# cenx4-rev2-2.net
KiCad netlist of a schematic drawn in EAGLE
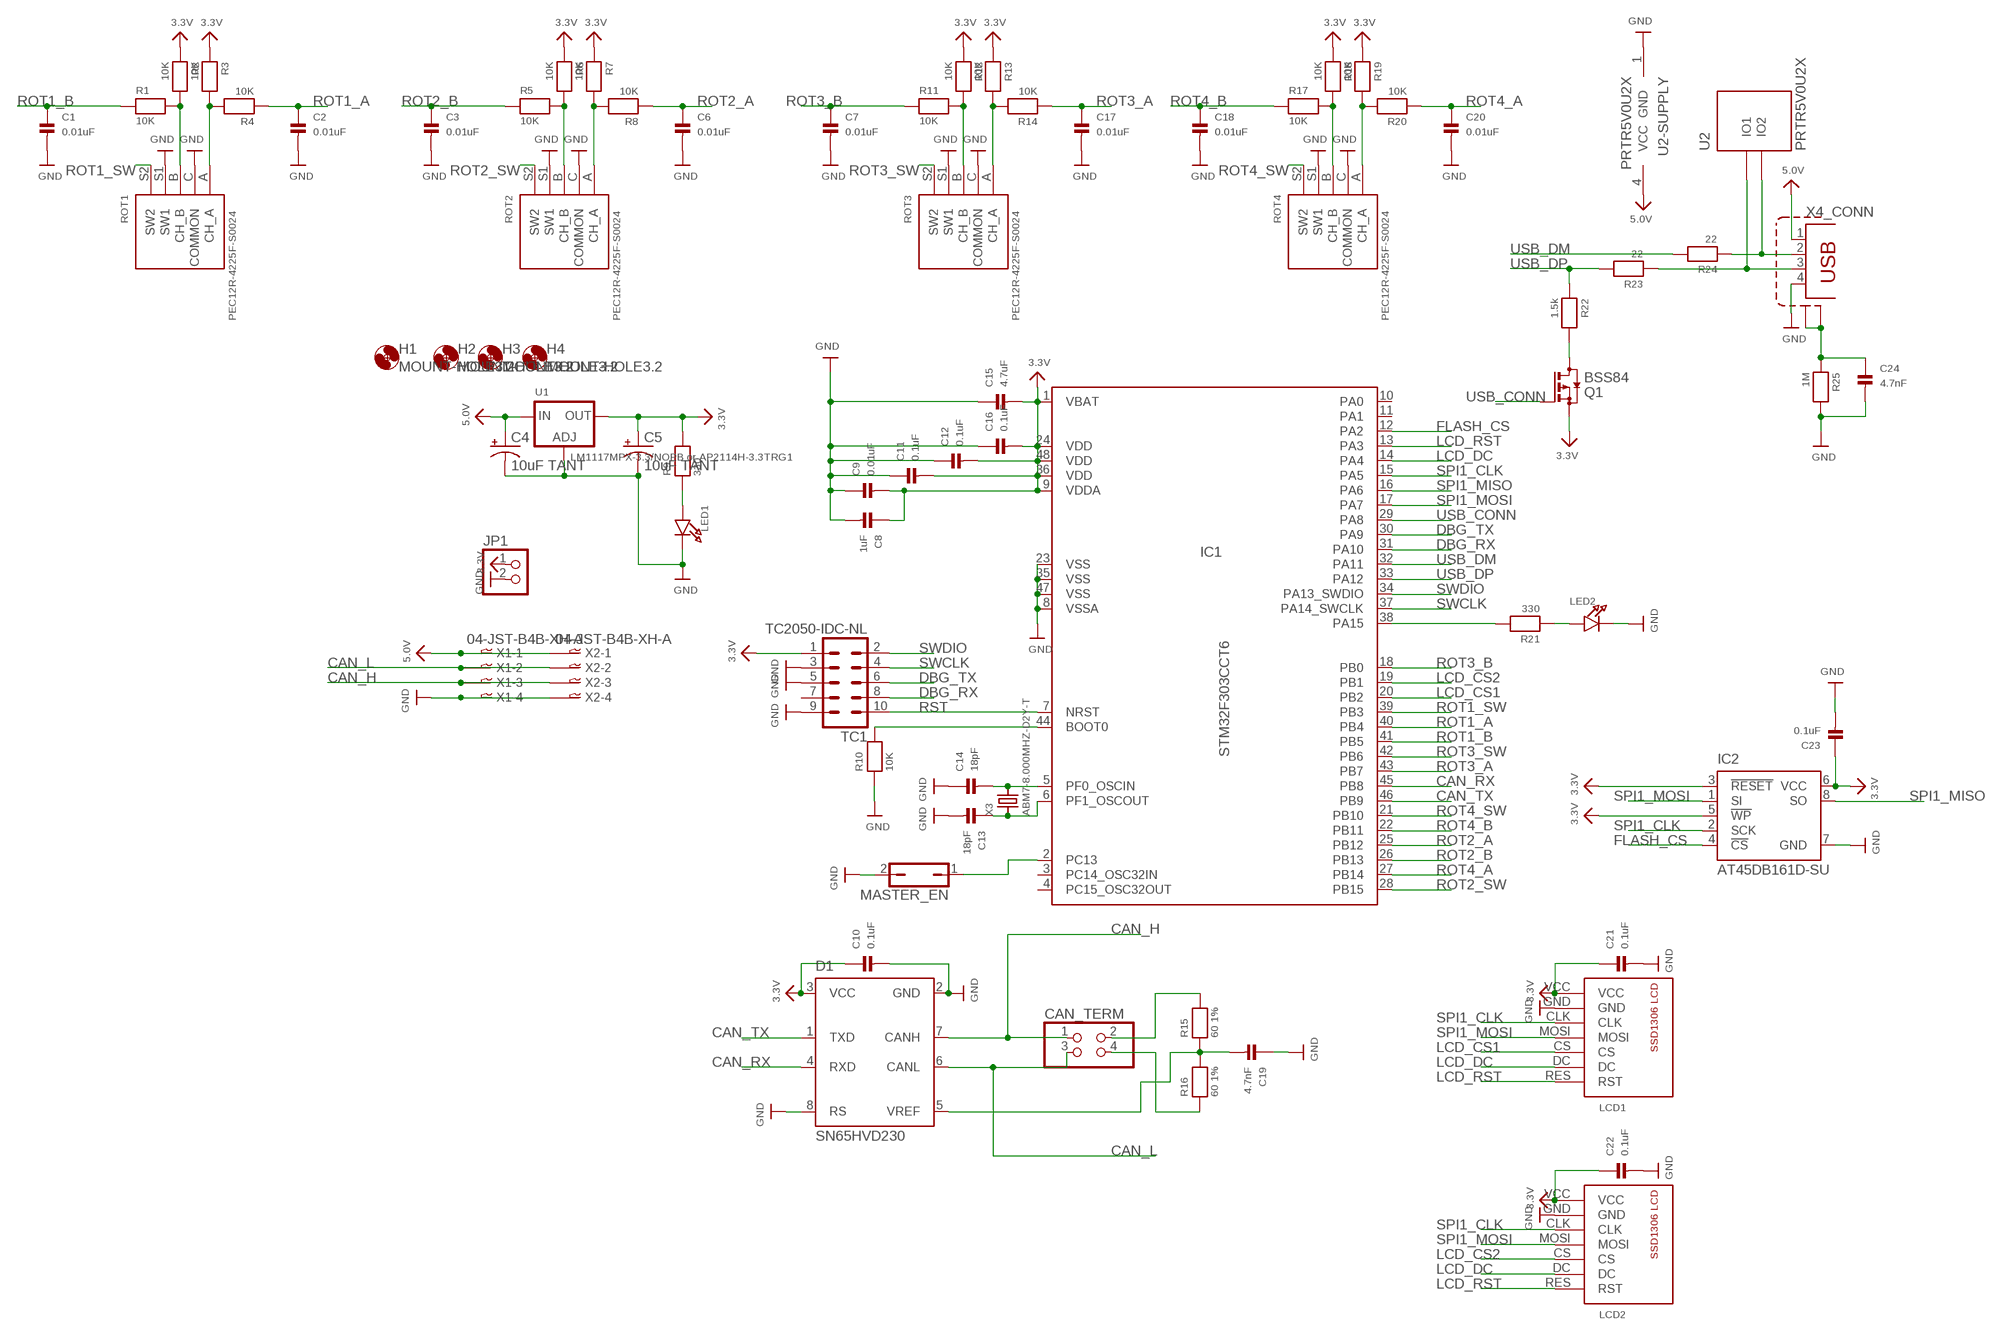
[diagram p0: schematic, sheet 1]

(export (version "E")
  (design (tool "Eeschema 10.0.6"))
  (components
    (comp (ref "C1")
      (value "0.01uF")
      (footprint "eagle-import:0603")
      (libsource (lib "eagle-import") (part "CAP_CERAMIC0603"))
    )
    (comp (ref "C2")
      (value "0.01uF")
      (footprint "eagle-import:0603")
      (libsource (lib "eagle-import") (part "CAP_CERAMIC0603"))
    )
    (comp (ref "C3")
      (value "0.01uF")
      (footprint "eagle-import:0603")
      (libsource (lib "eagle-import") (part "CAP_CERAMIC0603"))
    )
    (comp (ref "C4")
      (value "10uF TANT")
      (footprint "eagle-import:0603-POL")
      (libsource (lib "eagle-import") (part "10UF-6.3V-20%(0603)(TANT){dblquote}"))
    )
    (comp (ref "C5")
      (value "10uF TANT")
      (footprint "eagle-import:0603-POL")
      (libsource (lib "eagle-import") (part "10UF-6.3V-20%(0603)(TANT){dblquote}"))
    )
    (comp (ref "C6")
      (value "0.01uF")
      (footprint "eagle-import:0603")
      (libsource (lib "eagle-import") (part "CAP_CERAMIC0603"))
    )
    (comp (ref "C7")
      (value "0.01uF")
      (footprint "eagle-import:0603")
      (libsource (lib "eagle-import") (part "CAP_CERAMIC0603"))
    )
    (comp (ref "C8")
      (value "1uF")
      (footprint "eagle-import:0603")
      (libsource (lib "eagle-import") (part "CAP_CERAMIC0603"))
    )
    (comp (ref "C9")
      (value "0.01uF")
      (footprint "eagle-import:0603")
      (libsource (lib "eagle-import") (part "CAP_CERAMIC0603"))
    )
    (comp (ref "C10")
      (value "0.1uF")
      (footprint "eagle-import:0603")
      (libsource (lib "eagle-import") (part "CAP_CERAMIC0603"))
    )
    (comp (ref "C11")
      (value "0.1uF")
      (footprint "eagle-import:0603")
      (libsource (lib "eagle-import") (part "CAP_CERAMIC0603"))
    )
    (comp (ref "C12")
      (value "0.1uF")
      (footprint "eagle-import:0603")
      (libsource (lib "eagle-import") (part "CAP_CERAMIC0603"))
    )
    (comp (ref "C13")
      (value "18pF")
      (footprint "eagle-import:0603")
      (libsource (lib "eagle-import") (part "CAP_CERAMIC0603"))
    )
    (comp (ref "C14")
      (value "18pF")
      (footprint "eagle-import:0603")
      (libsource (lib "eagle-import") (part "CAP_CERAMIC0603"))
    )
    (comp (ref "C15")
      (value "4.7uF")
      (footprint "eagle-import:0603")
      (fields (field (name "MPN") "CL10A475MP5LNNC"))
      (libsource (lib "eagle-import") (part "CAP_CERAMIC0603"))
    )
    (comp (ref "C16")
      (value "0.1uF")
      (footprint "eagle-import:0603")
      (libsource (lib "eagle-import") (part "CAP_CERAMIC0603"))
    )
    (comp (ref "C17")
      (value "0.01uF")
      (footprint "eagle-import:0603")
      (libsource (lib "eagle-import") (part "CAP_CERAMIC0603"))
    )
    (comp (ref "C18")
      (value "0.01uF")
      (footprint "eagle-import:0603")
      (libsource (lib "eagle-import") (part "CAP_CERAMIC0603"))
    )
    (comp (ref "C19")
      (value "4.7nF")
      (footprint "eagle-import:0603")
      (libsource (lib "eagle-import") (part "CAP_CERAMIC0603"))
    )
    (comp (ref "C20")
      (value "0.01uF")
      (footprint "eagle-import:0603")
      (libsource (lib "eagle-import") (part "CAP_CERAMIC0603"))
    )
    (comp (ref "C21")
      (value "0.1uF")
      (footprint "eagle-import:0603")
      (libsource (lib "eagle-import") (part "CAP_CERAMIC0603"))
    )
    (comp (ref "C22")
      (value "0.1uF")
      (footprint "eagle-import:0603")
      (libsource (lib "eagle-import") (part "CAP_CERAMIC0603"))
    )
    (comp (ref "C23")
      (value "0.1uF")
      (footprint "eagle-import:0603")
      (libsource (lib "eagle-import") (part "CAP_CERAMIC0603"))
    )
    (comp (ref "C24")
      (value "4.7nF")
      (footprint "eagle-import:0603")
      (libsource (lib "eagle-import") (part "CAP_CERAMIC0603"))
    )
    (comp (ref "CAN_TERM")
      (value "PINHD-2X2")
      (footprint "eagle-import:2X02")
      (fields (field (name "MPN") "5-146254-2"))
      (libsource (lib "eagle-import") (part "PINHD-2X2"))
    )
    (comp (ref "D1")
      (value "SN65HVD230")
      (footprint "eagle-import:SO8")
      (fields (field (name "MPN") "SN65HVD230DR"))
      (libsource (lib "eagle-import") (part "SN65HVD230"))
    )
    (comp (ref "H1")
      (value "MOUNT-HOLE3.2")
      (footprint "eagle-import:3,2")
      (libsource (lib "eagle-import") (part "MOUNT-HOLE3.2"))
    )
    (comp (ref "H2")
      (value "MOUNT-HOLE3.2")
      (footprint "eagle-import:3,2")
      (libsource (lib "eagle-import") (part "MOUNT-HOLE3.2"))
    )
    (comp (ref "H3")
      (value "MOUNT-HOLE3.2")
      (footprint "eagle-import:3,2")
      (libsource (lib "eagle-import") (part "MOUNT-HOLE3.2"))
    )
    (comp (ref "H4")
      (value "MOUNT-HOLE3.2")
      (footprint "eagle-import:3,2")
      (libsource (lib "eagle-import") (part "MOUNT-HOLE3.2"))
    )
    (comp (ref "IC1")
      (value "STM32F303CCT6")
      (footprint "eagle-import:TQFP48")
      (libsource (lib "eagle-import") (part "STM32F302_F303_B_C_LQFP48"))
    )
    (comp (ref "IC2")
      (value "AT45DB161D-SU")
      (footprint "eagle-import:8S2")
      (fields (field (name "MF") "ATMEL"))
      (libsource (lib "eagle-import") (part "AT45DB161D-SU"))
    )
    (comp (ref "JP1")
      (value "PINHD-1X2")
      (footprint "eagle-import:1X02")
      (fields (field (name "MPN") "MF-CON-2.54mm-01x02"))
      (libsource (lib "eagle-import") (part "PINHD-1X2"))
    )
    (comp (ref "LCD1")
      (value "SSD1306-7PINWITHOUT-HOLES")
      (footprint "eagle-import:SSD1306-7PIN-NO-HOLES")
      (libsource (lib "eagle-import") (part "SSD1306-7PINWITHOUT-HOLES"))
    )
    (comp (ref "LCD2")
      (value "SSD1306-7PINWITHOUT-HOLES")
      (footprint "eagle-import:SSD1306-7PIN-NO-HOLES")
      (libsource (lib "eagle-import") (part "SSD1306-7PINWITHOUT-HOLES"))
    )
    (comp (ref "LED1")
      (value "LED0603")
      (footprint "eagle-import:CHIPLED_0603")
      (fields (field (name "MPN") "MF-LED-0603-GREEN"))
      (libsource (lib "eagle-import") (part "LED0603"))
    )
    (comp (ref "LED2")
      (value "LED0603")
      (footprint "eagle-import:CHIPLED_0603")
      (fields (field (name "MPN") "MF-LED-0603-GREEN"))
      (libsource (lib "eagle-import") (part "LED0603"))
    )
    (comp (ref "MASTER_EN")
      (value "JP1Q")
      (footprint "eagle-import:JP1")
      (fields (field (name "MPN") "MF-CON-2.54mm-01x02"))
      (libsource (lib "eagle-import") (part "JP1Q"))
    )
    (comp (ref "Q1")
      (value "BSS84")
      (footprint "eagle-import:SOT23")
      (libsource (lib "eagle-import") (part "BSS84"))
    )
    (comp (ref "R1")
      (value "10K")
      (footprint "eagle-import:0603")
      (libsource (lib "eagle-import") (part "RESISTOR0603"))
    )
    (comp (ref "R2")
      (value "10K")
      (footprint "eagle-import:0603")
      (libsource (lib "eagle-import") (part "RESISTOR0603"))
    )
    (comp (ref "R3")
      (value "10K")
      (footprint "eagle-import:0603")
      (libsource (lib "eagle-import") (part "RESISTOR0603"))
    )
    (comp (ref "R4")
      (value "10K")
      (footprint "eagle-import:0603")
      (libsource (lib "eagle-import") (part "RESISTOR0603"))
    )
    (comp (ref "R5")
      (value "10K")
      (footprint "eagle-import:0603")
      (libsource (lib "eagle-import") (part "RESISTOR0603"))
    )
    (comp (ref "R6")
      (value "10K")
      (footprint "eagle-import:0603")
      (libsource (lib "eagle-import") (part "RESISTOR0603"))
    )
    (comp (ref "R7")
      (value "10K")
      (footprint "eagle-import:0603")
      (libsource (lib "eagle-import") (part "RESISTOR0603"))
    )
    (comp (ref "R8")
      (value "10K")
      (footprint "eagle-import:0603")
      (libsource (lib "eagle-import") (part "RESISTOR0603"))
    )
    (comp (ref "R9")
      (value "330")
      (footprint "eagle-import:0603")
      (fields (field (name "MPN") "MF-RES-0603-330"))
      (libsource (lib "eagle-import") (part "RESISTOR0603"))
    )
    (comp (ref "R10")
      (value "10K")
      (footprint "eagle-import:0603")
      (libsource (lib "eagle-import") (part "RESISTOR0603"))
    )
    (comp (ref "R11")
      (value "10K")
      (footprint "eagle-import:0603")
      (libsource (lib "eagle-import") (part "RESISTOR0603"))
    )
    (comp (ref "R12")
      (value "10K")
      (footprint "eagle-import:0603")
      (libsource (lib "eagle-import") (part "RESISTOR0603"))
    )
    (comp (ref "R13")
      (value "10K")
      (footprint "eagle-import:0603")
      (libsource (lib "eagle-import") (part "RESISTOR0603"))
    )
    (comp (ref "R14")
      (value "10K")
      (footprint "eagle-import:0603")
      (libsource (lib "eagle-import") (part "RESISTOR0603"))
    )
    (comp (ref "R15")
      (value "60 1%")
      (footprint "eagle-import:0603")
      (fields (field (name "MPN") "MF-RES-0603-60.4"))
      (libsource (lib "eagle-import") (part "RESISTOR0603"))
    )
    (comp (ref "R16")
      (value "60 1%")
      (footprint "eagle-import:0603")
      (fields (field (name "MPN") "MF-RES-0603-60.4"))
      (libsource (lib "eagle-import") (part "RESISTOR0603"))
    )
    (comp (ref "R17")
      (value "10K")
      (footprint "eagle-import:0603")
      (libsource (lib "eagle-import") (part "RESISTOR0603"))
    )
    (comp (ref "R18")
      (value "10K")
      (footprint "eagle-import:0603")
      (libsource (lib "eagle-import") (part "RESISTOR0603"))
    )
    (comp (ref "R19")
      (value "10K")
      (footprint "eagle-import:0603")
      (libsource (lib "eagle-import") (part "RESISTOR0603"))
    )
    (comp (ref "R20")
      (value "10K")
      (footprint "eagle-import:0603")
      (libsource (lib "eagle-import") (part "RESISTOR0603"))
    )
    (comp (ref "R21")
      (value "330")
      (footprint "eagle-import:0603")
      (fields (field (name "MPN") "MF-RES-0603-330"))
      (libsource (lib "eagle-import") (part "RESISTOR0603"))
    )
    (comp (ref "R22")
      (value "1.5k")
      (footprint "eagle-import:0603")
      (fields (field (name "MPN") "MCR03ERTF1501"))
      (libsource (lib "eagle-import") (part "RESISTOR0603"))
    )
    (comp (ref "R23")
      (value "22")
      (footprint "eagle-import:0603")
      (fields (field (name "MPN") "MF-RES-0603-22"))
      (libsource (lib "eagle-import") (part "RESISTOR0603"))
    )
    (comp (ref "R24")
      (value "22")
      (footprint "eagle-import:0603")
      (fields (field (name "MPN") "MF-RES-0603-22"))
      (libsource (lib "eagle-import") (part "RESISTOR0603"))
    )
    (comp (ref "R25")
      (value "1M")
      (footprint "eagle-import:0603")
      (libsource (lib "eagle-import") (part "RESISTOR0603"))
    )
    (comp (ref "ROT1")
      (value "PEC12R-4225F-S0024")
      (footprint "eagle-import:PEC111-4XXXK-SXXXX")
      (libsource (lib "eagle-import") (part "PEC11-4215K-S0024"))
    )
    (comp (ref "ROT2")
      (value "PEC12R-4225F-S0024")
      (footprint "eagle-import:PEC111-4XXXK-SXXXX")
      (libsource (lib "eagle-import") (part "PEC11-4215K-S0024"))
    )
    (comp (ref "ROT3")
      (value "PEC12R-4225F-S0024")
      (footprint "eagle-import:PEC111-4XXXK-SXXXX")
      (libsource (lib "eagle-import") (part "PEC11-4215K-S0024"))
    )
    (comp (ref "ROT4")
      (value "PEC12R-4225F-S0024")
      (footprint "eagle-import:PEC111-4XXXK-SXXXX")
      (libsource (lib "eagle-import") (part "PEC11-4215K-S0024"))
    )
    (comp (ref "TC1")
      (value "TC2050-IDC-NL")
      (footprint "eagle-import:TC2050-IDC-NL")
      (libsource (lib "eagle-import") (part "TC2050-IDC-NL"))
    )
    (comp (ref "U1")
      (value "LM1117MPX-3.3/NOPB or AP2114H-3.3TRG1")
      (footprint "eagle-import:SOT223-R")
      (fields (field (name "MPN") "LM1117MPX-3.3/NOPB"))
      (libsource (lib "eagle-import") (part "LM1117SOT223-REFLOW"))
    )
    (comp (ref "U2")
      (value "PRTR5V0U2X")
      (footprint "eagle-import:SOT-143B")
      (fields (field (name "MANUFACTURER") "NXP Semiconductors") (field (name "MPN") "PRTR5V0U2X,215"))
      (libsource (lib "eagle-import") (part "PRTR5V0U2X?"))
    )
    (comp (ref "X1")
      (value "04-JST-B4B-XH-A")
      (footprint "eagle-import:B4B-XH")
      (fields (field (name "MPN") "B4B-XH-A(LF)(SN)"))
      (libsource (lib "eagle-import") (part "04-JST-B4B-XH-A"))
    )
    (comp (ref "X2")
      (value "04-JST-B4B-XH-A")
      (footprint "eagle-import:B4B-XH")
      (fields (field (name "MPN") "B4B-XH-A(LF)(SN)"))
      (libsource (lib "eagle-import") (part "04-JST-B4B-XH-A"))
    )
    (comp (ref "X3")
      (value "ABM7-8.000MHZ-D2Y-T")
      (footprint "eagle-import:ABM7-8.000MHZ-D2Y-T")
      (libsource (lib "eagle-import") (part "ABM7-8.000MHZ-D2Y-T"))
    )
    (comp (ref "X4")
      (value "TE-292304-1")
      (footprint "eagle-import:TE-292304-1")
      (fields (field (name "MPN") "292304-1 ") (field (name "POPULATE") "0"))
      (libsource (lib "eagle-import") (part "TE-292304-1"))
    )
  )
  (nets
    (net (code "1") (name "/CAN_H") (class "Default")
      (node (ref "CAN_TERM") (pin "1") (pinfunction "1_1") (pintype "passive"))
      (node (ref "D1") (pin "7") (pinfunction "CANH_7") (pintype "bidirectional"))
      (node (ref "X1") (pin "P$3") (pinfunction "1_P$3") (pintype "passive"))
      (node (ref "X2") (pin "P$3") (pinfunction "1_P$3") (pintype "passive"))
    )
    (net (code "2") (name "/CAN_L") (class "Default")
      (node (ref "CAN_TERM") (pin "3") (pinfunction "3_3") (pintype "passive"))
      (node (ref "D1") (pin "6") (pinfunction "CANL_6") (pintype "bidirectional"))
      (node (ref "X1") (pin "P$2") (pinfunction "1_P$2") (pintype "passive"))
      (node (ref "X2") (pin "P$2") (pinfunction "1_P$2") (pintype "passive"))
    )
    (net (code "3") (name "/CAN_RX") (class "Default")
      (node (ref "D1") (pin "4") (pinfunction "RXD_4") (pintype "output"))
      (node (ref "IC1") (pin "45") (pinfunction "PB8_45") (pintype "bidirectional"))
    )
    (net (code "4") (name "/CAN_TX") (class "Default")
      (node (ref "D1") (pin "1") (pinfunction "TXD_1") (pintype "input"))
      (node (ref "IC1") (pin "46") (pinfunction "PB9_46") (pintype "bidirectional"))
    )
    (net (code "5") (name "/DBG_RX") (class "Default")
      (node (ref "IC1") (pin "31") (pinfunction "PA10_31") (pintype "bidirectional"))
      (node (ref "TC1") (pin "8") (pinfunction "8_8") (pintype "passive"))
    )
    (net (code "6") (name "/DBG_TX") (class "Default")
      (node (ref "IC1") (pin "30") (pinfunction "PA9_30") (pintype "bidirectional"))
      (node (ref "TC1") (pin "6") (pinfunction "6_6") (pintype "passive"))
    )
    (net (code "7") (name "/FLASH_CS") (class "Default")
      (node (ref "IC1") (pin "12") (pinfunction "PA2_12") (pintype "bidirectional"))
      (node (ref "IC2") (pin "4") (pinfunction "~{CS}_4") (pintype "input"))
    )
    (net (code "8") (name "/LCD_CS1") (class "Default")
      (node (ref "IC1") (pin "20") (pinfunction "PB2_20") (pintype "bidirectional"))
      (node (ref "LCD1") (pin "CS") (pinfunction "CS_CS") (pintype "bidirectional"))
    )
    (net (code "9") (name "/LCD_CS2") (class "Default")
      (node (ref "IC1") (pin "19") (pinfunction "PB1_19") (pintype "bidirectional"))
      (node (ref "LCD2") (pin "CS") (pinfunction "CS_CS") (pintype "bidirectional"))
    )
    (net (code "10") (name "/LCD_DC") (class "Default")
      (node (ref "IC1") (pin "14") (pinfunction "PA4_14") (pintype "bidirectional"))
      (node (ref "LCD1") (pin "DC") (pinfunction "DC_DC") (pintype "bidirectional"))
      (node (ref "LCD2") (pin "DC") (pinfunction "DC_DC") (pintype "bidirectional"))
    )
    (net (code "11") (name "/LCD_RST") (class "Default")
      (node (ref "IC1") (pin "13") (pinfunction "PA3_13") (pintype "bidirectional"))
      (node (ref "LCD1") (pin "RES") (pinfunction "RST_RES") (pintype "bidirectional"))
      (node (ref "LCD2") (pin "RES") (pinfunction "RST_RES") (pintype "bidirectional"))
    )
    (net (code "12") (name "/ROT1_A") (class "Default")
      (node (ref "C2") (pin "1") (pinfunction "P$1_1") (pintype "passive"))
      (node (ref "IC1") (pin "40") (pinfunction "PB4_40") (pintype "input"))
      (node (ref "R4") (pin "1") (pinfunction "1_1") (pintype "passive"))
    )
    (net (code "13") (name "/ROT1_B") (class "Default")
      (node (ref "C1") (pin "1") (pinfunction "P$1_1") (pintype "passive"))
      (node (ref "IC1") (pin "41") (pinfunction "PB5_41") (pintype "bidirectional"))
      (node (ref "R1") (pin "1") (pinfunction "1_1") (pintype "passive"))
    )
    (net (code "14") (name "/ROT1_SW") (class "Default")
      (node (ref "IC1") (pin "39") (pinfunction "PB3_39") (pintype "output"))
      (node (ref "ROT1") (pin "S2") (pinfunction "SW2_S2") (pintype "bidirectional"))
    )
    (net (code "15") (name "/ROT2_A") (class "Default")
      (node (ref "C6") (pin "1") (pinfunction "P$1_1") (pintype "passive"))
      (node (ref "IC1") (pin "25") (pinfunction "PB12_25") (pintype "bidirectional"))
      (node (ref "R8") (pin "1") (pinfunction "1_1") (pintype "passive"))
    )
    (net (code "16") (name "/ROT2_B") (class "Default")
      (node (ref "C3") (pin "1") (pinfunction "P$1_1") (pintype "passive"))
      (node (ref "IC1") (pin "26") (pinfunction "PB13_26") (pintype "bidirectional"))
      (node (ref "R5") (pin "1") (pinfunction "1_1") (pintype "passive"))
    )
    (net (code "17") (name "/ROT2_SW") (class "Default")
      (node (ref "IC1") (pin "28") (pinfunction "PB15_28") (pintype "bidirectional"))
      (node (ref "ROT2") (pin "S2") (pinfunction "SW2_S2") (pintype "bidirectional"))
    )
    (net (code "18") (name "/ROT3_A") (class "Default")
      (node (ref "C17") (pin "1") (pinfunction "P$1_1") (pintype "passive"))
      (node (ref "IC1") (pin "43") (pinfunction "PB7_43") (pintype "bidirectional"))
      (node (ref "R14") (pin "1") (pinfunction "1_1") (pintype "passive"))
    )
    (net (code "19") (name "/ROT3_B") (class "Default")
      (node (ref "C7") (pin "1") (pinfunction "P$1_1") (pintype "passive"))
      (node (ref "IC1") (pin "18") (pinfunction "PB0_18") (pintype "bidirectional"))
      (node (ref "R11") (pin "1") (pinfunction "1_1") (pintype "passive"))
    )
    (net (code "20") (name "/ROT3_SW") (class "Default")
      (node (ref "IC1") (pin "42") (pinfunction "PB6_42") (pintype "bidirectional"))
      (node (ref "ROT3") (pin "S2") (pinfunction "SW2_S2") (pintype "bidirectional"))
    )
    (net (code "21") (name "/ROT4_A") (class "Default")
      (node (ref "C20") (pin "1") (pinfunction "P$1_1") (pintype "passive"))
      (node (ref "IC1") (pin "27") (pinfunction "PB14_27") (pintype "bidirectional"))
      (node (ref "R20") (pin "1") (pinfunction "1_1") (pintype "passive"))
    )
    (net (code "22") (name "/ROT4_B") (class "Default")
      (node (ref "C18") (pin "1") (pinfunction "P$1_1") (pintype "passive"))
      (node (ref "IC1") (pin "22") (pinfunction "PB11_22") (pintype "bidirectional"))
      (node (ref "R17") (pin "1") (pinfunction "1_1") (pintype "passive"))
    )
    (net (code "23") (name "/ROT4_SW") (class "Default")
      (node (ref "IC1") (pin "21") (pinfunction "PB10_21") (pintype "bidirectional"))
      (node (ref "ROT4") (pin "S2") (pinfunction "SW2_S2") (pintype "bidirectional"))
    )
    (net (code "24") (name "/RST") (class "Default")
      (node (ref "IC1") (pin "7") (pinfunction "NRST_7") (pintype "input"))
      (node (ref "TC1") (pin "10") (pinfunction "10_10") (pintype "passive"))
    )
    (net (code "25") (name "/SPI1_CLK") (class "Default")
      (node (ref "IC1") (pin "15") (pinfunction "PA5_15") (pintype "bidirectional"))
      (node (ref "IC2") (pin "2") (pinfunction "SCK_2") (pintype "input"))
      (node (ref "LCD1") (pin "CLK") (pinfunction "CLK_CLK") (pintype "bidirectional"))
      (node (ref "LCD2") (pin "CLK") (pinfunction "CLK_CLK") (pintype "bidirectional"))
    )
    (net (code "26") (name "/SPI1_MISO") (class "Default")
      (node (ref "IC1") (pin "16") (pinfunction "PA6_16") (pintype "bidirectional"))
      (node (ref "IC2") (pin "8") (pinfunction "SO_8") (pintype "output"))
    )
    (net (code "27") (name "/SPI1_MOSI") (class "Default")
      (node (ref "IC1") (pin "17") (pinfunction "PA7_17") (pintype "bidirectional"))
      (node (ref "IC2") (pin "1") (pinfunction "SI_1") (pintype "input"))
      (node (ref "LCD1") (pin "MOSI") (pinfunction "MOSI_MOSI") (pintype "bidirectional"))
      (node (ref "LCD2") (pin "MOSI") (pinfunction "MOSI_MOSI") (pintype "bidirectional"))
    )
    (net (code "28") (name "/SWCLK") (class "Default")
      (node (ref "IC1") (pin "37") (pinfunction "PA14_SWCLK_37") (pintype "input"))
      (node (ref "TC1") (pin "4") (pinfunction "4_4") (pintype "passive"))
    )
    (net (code "29") (name "/SWDIO") (class "Default")
      (node (ref "IC1") (pin "34") (pinfunction "PA13_SWDIO_34") (pintype "input"))
      (node (ref "TC1") (pin "2") (pinfunction "2_2") (pintype "passive"))
    )
    (net (code "30") (name "/USB_CONN") (class "Default")
      (node (ref "IC1") (pin "29") (pinfunction "PA8_29") (pintype "bidirectional"))
      (node (ref "Q1") (pin "1") (pinfunction "G_1") (pintype "passive"))
    )
    (net (code "31") (name "/USB_DM") (class "Default")
      (node (ref "IC1") (pin "32") (pinfunction "PA11_32") (pintype "bidirectional"))
      (node (ref "R24") (pin "2") (pinfunction "2_2") (pintype "passive"))
    )
    (net (code "32") (name "/USB_DP") (class "Default")
      (node (ref "IC1") (pin "33") (pinfunction "PA12_33") (pintype "bidirectional"))
      (node (ref "R22") (pin "1") (pinfunction "1_1") (pintype "passive"))
      (node (ref "R23") (pin "2") (pinfunction "2_2") (pintype "passive"))
    )
    (net (code "33") (name "3.3V") (class "Default")
      (node (ref "C10") (pin "1") (pinfunction "P$1_1") (pintype "passive"))
      (node (ref "C11") (pin "2") (pinfunction "P$2_2") (pintype "passive"))
      (node (ref "C12") (pin "2") (pinfunction "P$2_2") (pintype "passive"))
      (node (ref "C15") (pin "2") (pinfunction "P$2_2") (pintype "passive"))
      (node (ref "C16") (pin "2") (pinfunction "P$2_2") (pintype "passive"))
      (node (ref "C21") (pin "1") (pinfunction "P$1_1") (pintype "passive"))
      (node (ref "C22") (pin "1") (pinfunction "P$1_1") (pintype "passive"))
      (node (ref "C23") (pin "1") (pinfunction "P$1_1") (pintype "passive"))
      (node (ref "C5") (pin "A") (pinfunction "+_A") (pintype "passive"))
      (node (ref "C8") (pin "1") (pinfunction "P$1_1") (pintype "passive"))
      (node (ref "C9") (pin "2") (pinfunction "P$2_2") (pintype "passive"))
      (node (ref "D1") (pin "3") (pinfunction "VCC_3") (pintype "power_in"))
      (node (ref "IC1") (pin "1") (pinfunction "VBAT_1") (pintype "passive"))
      (node (ref "IC1") (pin "24") (pinfunction "VDD_24") (pintype "power_in"))
      (node (ref "IC1") (pin "36") (pinfunction "VDD_36") (pintype "power_in"))
      (node (ref "IC1") (pin "48") (pinfunction "VDD_48") (pintype "power_in"))
      (node (ref "IC1") (pin "9") (pinfunction "VDDA_9") (pintype "power_in"))
      (node (ref "IC2") (pin "3") (pinfunction "~{RESET}_3") (pintype "input"))
      (node (ref "IC2") (pin "5") (pinfunction "~{WP}_5") (pintype "input"))
      (node (ref "IC2") (pin "6") (pinfunction "VCC_6") (pintype "power_in"))
      (node (ref "JP1") (pin "1") (pinfunction "1_1") (pintype "passive"))
      (node (ref "LCD1") (pin "VCC") (pinfunction "VCC_VCC") (pintype "bidirectional"))
      (node (ref "LCD2") (pin "VCC") (pinfunction "VCC_VCC") (pintype "bidirectional"))
      (node (ref "Q1") (pin "2") (pinfunction "S_2") (pintype "passive"))
      (node (ref "R12") (pin "1") (pinfunction "1_1") (pintype "passive"))
      (node (ref "R13") (pin "1") (pinfunction "1_1") (pintype "passive"))
      (node (ref "R18") (pin "1") (pinfunction "1_1") (pintype "passive"))
      (node (ref "R19") (pin "1") (pinfunction "1_1") (pintype "passive"))
      (node (ref "R2") (pin "1") (pinfunction "1_1") (pintype "passive"))
      (node (ref "R3") (pin "1") (pinfunction "1_1") (pintype "passive"))
      (node (ref "R6") (pin "1") (pinfunction "1_1") (pintype "passive"))
      (node (ref "R7") (pin "1") (pinfunction "1_1") (pintype "passive"))
      (node (ref "R9") (pin "2") (pinfunction "2_2") (pintype "passive"))
      (node (ref "TC1") (pin "1") (pinfunction "1_1") (pintype "passive"))
      (node (ref "U1") (pin "2") (pinfunction "OUT_2") (pintype "passive"))
    )
    (net (code "34") (name "5.0V") (class "Default")
      (node (ref "C4") (pin "A") (pinfunction "+_A") (pintype "passive"))
      (node (ref "U1") (pin "3") (pinfunction "IN_3") (pintype "input"))
      (node (ref "U2") (pin "4") (pinfunction "VCC_4") (pintype "bidirectional"))
      (node (ref "X1") (pin "P$1") (pinfunction "1_P$1") (pintype "passive"))
      (node (ref "X2") (pin "P$1") (pinfunction "1_P$1") (pintype "passive"))
      (node (ref "X4") (pin "1") (pinfunction "1_1") (pintype "bidirectional"))
    )
    (net (code "35") (name "GND") (class "Default")
      (node (ref "C1") (pin "2") (pinfunction "P$2_2") (pintype "passive"))
      (node (ref "C10") (pin "2") (pinfunction "P$2_2") (pintype "passive"))
      (node (ref "C11") (pin "1") (pinfunction "P$1_1") (pintype "passive"))
      (node (ref "C12") (pin "1") (pinfunction "P$1_1") (pintype "passive"))
      (node (ref "C13") (pin "2") (pinfunction "P$2_2") (pintype "passive"))
      (node (ref "C14") (pin "1") (pinfunction "P$1_1") (pintype "passive"))
      (node (ref "C15") (pin "1") (pinfunction "P$1_1") (pintype "passive"))
      (node (ref "C16") (pin "1") (pinfunction "P$1_1") (pintype "passive"))
      (node (ref "C17") (pin "2") (pinfunction "P$2_2") (pintype "passive"))
      (node (ref "C18") (pin "2") (pinfunction "P$2_2") (pintype "passive"))
      (node (ref "C19") (pin "1") (pinfunction "P$1_1") (pintype "passive"))
      (node (ref "C2") (pin "2") (pinfunction "P$2_2") (pintype "passive"))
      (node (ref "C20") (pin "2") (pinfunction "P$2_2") (pintype "passive"))
      (node (ref "C21") (pin "2") (pinfunction "P$2_2") (pintype "passive"))
      (node (ref "C22") (pin "2") (pinfunction "P$2_2") (pintype "passive"))
      (node (ref "C23") (pin "2") (pinfunction "P$2_2") (pintype "passive"))
      (node (ref "C24") (pin "2") (pinfunction "P$2_2") (pintype "passive"))
      (node (ref "C3") (pin "2") (pinfunction "P$2_2") (pintype "passive"))
      (node (ref "C4") (pin "K") (pinfunction "-_K") (pintype "passive"))
      (node (ref "C5") (pin "K") (pinfunction "-_K") (pintype "passive"))
      (node (ref "C6") (pin "2") (pinfunction "P$2_2") (pintype "passive"))
      (node (ref "C7") (pin "2") (pinfunction "P$2_2") (pintype "passive"))
      (node (ref "C8") (pin "2") (pinfunction "P$2_2") (pintype "passive"))
      (node (ref "C9") (pin "1") (pinfunction "P$1_1") (pintype "passive"))
      (node (ref "D1") (pin "2") (pinfunction "GND_2") (pintype "power_in"))
      (node (ref "D1") (pin "8") (pinfunction "RS_8") (pintype "input"))
      (node (ref "IC1") (pin "23") (pinfunction "VSS_23") (pintype "power_in"))
      (node (ref "IC1") (pin "35") (pinfunction "VSS_35") (pintype "power_in"))
      (node (ref "IC1") (pin "47") (pinfunction "VSS_47") (pintype "power_in"))
      (node (ref "IC1") (pin "8") (pinfunction "VSSA_8") (pintype "power_in"))
      (node (ref "IC2") (pin "7") (pinfunction "GND_7") (pintype "power_in"))
      (node (ref "JP1") (pin "2") (pinfunction "2_2") (pintype "passive"))
      (node (ref "LCD1") (pin "GND") (pinfunction "GND_GND") (pintype "bidirectional"))
      (node (ref "LCD2") (pin "GND") (pinfunction "GND_GND") (pintype "bidirectional"))
      (node (ref "LED1") (pin "C") (pinfunction "C_C") (pintype "passive"))
      (node (ref "LED2") (pin "C") (pinfunction "C_C") (pintype "passive"))
      (node (ref "MASTER_EN") (pin "2") (pinfunction "2_2") (pintype "passive"))
      (node (ref "R10") (pin "1") (pinfunction "1_1") (pintype "passive"))
      (node (ref "R25") (pin "2") (pinfunction "2_2") (pintype "passive"))
      (node (ref "ROT1") (pin "C") (pinfunction "COMMON_C") (pintype "input"))
      (node (ref "ROT1") (pin "S1") (pinfunction "SW1_S1") (pintype "bidirectional"))
      (node (ref "ROT2") (pin "C") (pinfunction "COMMON_C") (pintype "input"))
      (node (ref "ROT2") (pin "S1") (pinfunction "SW1_S1") (pintype "bidirectional"))
      (node (ref "ROT3") (pin "C") (pinfunction "COMMON_C") (pintype "input"))
      (node (ref "ROT3") (pin "S1") (pinfunction "SW1_S1") (pintype "bidirectional"))
      (node (ref "ROT4") (pin "C") (pinfunction "COMMON_C") (pintype "input"))
      (node (ref "ROT4") (pin "S1") (pinfunction "SW1_S1") (pintype "bidirectional"))
      (node (ref "TC1") (pin "3") (pinfunction "3_3") (pintype "passive"))
      (node (ref "TC1") (pin "5") (pinfunction "5_5") (pintype "passive"))
      (node (ref "TC1") (pin "9") (pinfunction "9_9") (pintype "passive"))
      (node (ref "U1") (pin "1") (pinfunction "ADJ_1") (pintype "input"))
      (node (ref "U2") (pin "1") (pinfunction "GND_1") (pintype "bidirectional"))
      (node (ref "X1") (pin "P$4") (pinfunction "1_P$4") (pintype "passive"))
      (node (ref "X2") (pin "P$4") (pinfunction "1_P$4") (pintype "passive"))
      (node (ref "X4") (pin "4") (pinfunction "4_4") (pintype "bidirectional"))
    )
    (net (code "36") (name "Net-(C13-P$1)") (class "Default")
      (node (ref "C13") (pin "1") (pinfunction "P$1_1") (pintype "passive"))
      (node (ref "IC1") (pin "6") (pinfunction "PF1_OSCOUT_6") (pintype "bidirectional"))
      (node (ref "X3") (pin "P$1") (pinfunction "1_P$1") (pintype "passive"))
    )
    (net (code "37") (name "Net-(C14-P$2)") (class "Default")
      (node (ref "C14") (pin "2") (pinfunction "P$2_2") (pintype "passive"))
      (node (ref "IC1") (pin "5") (pinfunction "PF0_OSCIN_5") (pintype "bidirectional"))
      (node (ref "X3") (pin "P$2") (pinfunction "2_P$2") (pintype "passive"))
    )
    (net (code "38") (name "Net-(C19-P$2)") (class "Default")
      (node (ref "C19") (pin "2") (pinfunction "P$2_2") (pintype "passive"))
      (node (ref "D1") (pin "5") (pinfunction "VREF_5") (pintype "output"))
      (node (ref "R15") (pin "1") (pinfunction "1_1") (pintype "passive"))
      (node (ref "R16") (pin "2") (pinfunction "2_2") (pintype "passive"))
    )
    (net (code "39") (name "Net-(C24-P$1)") (class "Default")
      (node (ref "C24") (pin "1") (pinfunction "P$1_1") (pintype "passive"))
      (node (ref "R25") (pin "1") (pinfunction "1_1") (pintype "passive"))
      (node (ref "X4") (pin "P$1") (pinfunction "S1_P$1") (pintype "passive"))
      (node (ref "X4") (pin "P$2") (pinfunction "S2_P$2") (pintype "passive"))
    )
    (net (code "40") (name "Net-(CAN_TERM-Pad2)") (class "Default")
      (node (ref "CAN_TERM") (pin "2") (pinfunction "2_2") (pintype "passive"))
      (node (ref "R15") (pin "2") (pinfunction "2_2") (pintype "passive"))
    )
    (net (code "41") (name "Net-(CAN_TERM-Pad4)") (class "Default")
      (node (ref "CAN_TERM") (pin "4") (pinfunction "4_4") (pintype "passive"))
      (node (ref "R16") (pin "1") (pinfunction "1_1") (pintype "passive"))
    )
    (net (code "42") (name "Net-(IC1-BOOT0)") (class "Default")
      (node (ref "IC1") (pin "44") (pinfunction "BOOT0_44") (pintype "input"))
      (node (ref "R10") (pin "2") (pinfunction "2_2") (pintype "passive"))
    )
    (net (code "43") (name "Net-(IC1-PA15)") (class "Default")
      (node (ref "IC1") (pin "38") (pinfunction "PA15_38") (pintype "input"))
      (node (ref "R21") (pin "2") (pinfunction "2_2") (pintype "passive"))
    )
    (net (code "44") (name "Net-(IC1-PC13)") (class "Default")
      (node (ref "IC1") (pin "2") (pinfunction "PC13_2") (pintype "bidirectional"))
      (node (ref "MASTER_EN") (pin "1") (pinfunction "1_1") (pintype "passive"))
    )
    (net (code "45") (name "Net-(LED1-PadA)") (class "Default")
      (node (ref "LED1") (pin "A") (pinfunction "A_A") (pintype "passive"))
      (node (ref "R9") (pin "1") (pinfunction "1_1") (pintype "passive"))
    )
    (net (code "46") (name "Net-(LED2-PadA)") (class "Default")
      (node (ref "LED2") (pin "A") (pinfunction "A_A") (pintype "passive"))
      (node (ref "R21") (pin "1") (pinfunction "1_1") (pintype "passive"))
    )
    (net (code "47") (name "Net-(Q1-D)") (class "Default")
      (node (ref "Q1") (pin "3") (pinfunction "D_3") (pintype "passive"))
      (node (ref "R22") (pin "2") (pinfunction "2_2") (pintype "passive"))
    )
    (net (code "48") (name "Net-(ROT1-CH_A)") (class "Default")
      (node (ref "R3") (pin "2") (pinfunction "2_2") (pintype "passive"))
      (node (ref "R4") (pin "2") (pinfunction "2_2") (pintype "passive"))
      (node (ref "ROT1") (pin "A") (pinfunction "CH_A_A") (pintype "output"))
    )
    (net (code "49") (name "Net-(ROT1-CH_B)") (class "Default")
      (node (ref "R1") (pin "2") (pinfunction "2_2") (pintype "passive"))
      (node (ref "R2") (pin "2") (pinfunction "2_2") (pintype "passive"))
      (node (ref "ROT1") (pin "B") (pinfunction "CH_B_B") (pintype "output"))
    )
    (net (code "50") (name "Net-(ROT2-CH_A)") (class "Default")
      (node (ref "R7") (pin "2") (pinfunction "2_2") (pintype "passive"))
      (node (ref "R8") (pin "2") (pinfunction "2_2") (pintype "passive"))
      (node (ref "ROT2") (pin "A") (pinfunction "CH_A_A") (pintype "output"))
    )
    (net (code "51") (name "Net-(ROT2-CH_B)") (class "Default")
      (node (ref "R5") (pin "2") (pinfunction "2_2") (pintype "passive"))
      (node (ref "R6") (pin "2") (pinfunction "2_2") (pintype "passive"))
      (node (ref "ROT2") (pin "B") (pinfunction "CH_B_B") (pintype "output"))
    )
    (net (code "52") (name "Net-(ROT3-CH_A)") (class "Default")
      (node (ref "R13") (pin "2") (pinfunction "2_2") (pintype "passive"))
      (node (ref "R14") (pin "2") (pinfunction "2_2") (pintype "passive"))
      (node (ref "ROT3") (pin "A") (pinfunction "CH_A_A") (pintype "output"))
    )
    (net (code "53") (name "Net-(ROT3-CH_B)") (class "Default")
      (node (ref "R11") (pin "2") (pinfunction "2_2") (pintype "passive"))
      (node (ref "R12") (pin "2") (pinfunction "2_2") (pintype "passive"))
      (node (ref "ROT3") (pin "B") (pinfunction "CH_B_B") (pintype "output"))
    )
    (net (code "54") (name "Net-(ROT4-CH_A)") (class "Default")
      (node (ref "R19") (pin "2") (pinfunction "2_2") (pintype "passive"))
      (node (ref "R20") (pin "2") (pinfunction "2_2") (pintype "passive"))
      (node (ref "ROT4") (pin "A") (pinfunction "CH_A_A") (pintype "output"))
    )
    (net (code "55") (name "Net-(ROT4-CH_B)") (class "Default")
      (node (ref "R17") (pin "2") (pinfunction "2_2") (pintype "passive"))
      (node (ref "R18") (pin "2") (pinfunction "2_2") (pintype "passive"))
      (node (ref "ROT4") (pin "B") (pinfunction "CH_B_B") (pintype "output"))
    )
    (net (code "56") (name "Net-(U2B-IO1)") (class "Default")
      (node (ref "R23") (pin "1") (pinfunction "1_1") (pintype "passive"))
      (node (ref "U2") (pin "2") (pinfunction "IO1_2") (pintype "bidirectional"))
      (node (ref "X4") (pin "3") (pinfunction "3_3") (pintype "bidirectional"))
    )
    (net (code "57") (name "Net-(U2B-IO2)") (class "Default")
      (node (ref "R24") (pin "1") (pinfunction "1_1") (pintype "passive"))
      (node (ref "U2") (pin "3") (pinfunction "IO2_3") (pintype "bidirectional"))
      (node (ref "X4") (pin "2") (pinfunction "2_2") (pintype "bidirectional"))
    )
    (net (code "58") (name "unconnected-(IC1-PA0-Pad10)") (class "Default")
      (node (ref "IC1") (pin "10") (pinfunction "PA0_10") (pintype "bidirectional"))
    )
    (net (code "59") (name "unconnected-(IC1-PA1-Pad11)") (class "Default")
      (node (ref "IC1") (pin "11") (pinfunction "PA1_11") (pintype "bidirectional"))
    )
    (net (code "60") (name "unconnected-(IC1-PC14_OSC32IN-Pad3)") (class "Default")
      (node (ref "IC1") (pin "3") (pinfunction "PC14_OSC32IN_3") (pintype "bidirectional"))
    )
    (net (code "61") (name "unconnected-(IC1-PC15_OSC32OUT-Pad4)") (class "Default")
      (node (ref "IC1") (pin "4") (pinfunction "PC15_OSC32OUT_4") (pintype "bidirectional"))
    )
    (net (code "62") (name "unconnected-(TC1-Pad7)") (class "Default")
      (node (ref "TC1") (pin "7") (pinfunction "7_7") (pintype "passive"))
    )
  )
)
